# Speaker.net
KiCad netlist of a schematic drawn in EAGLE
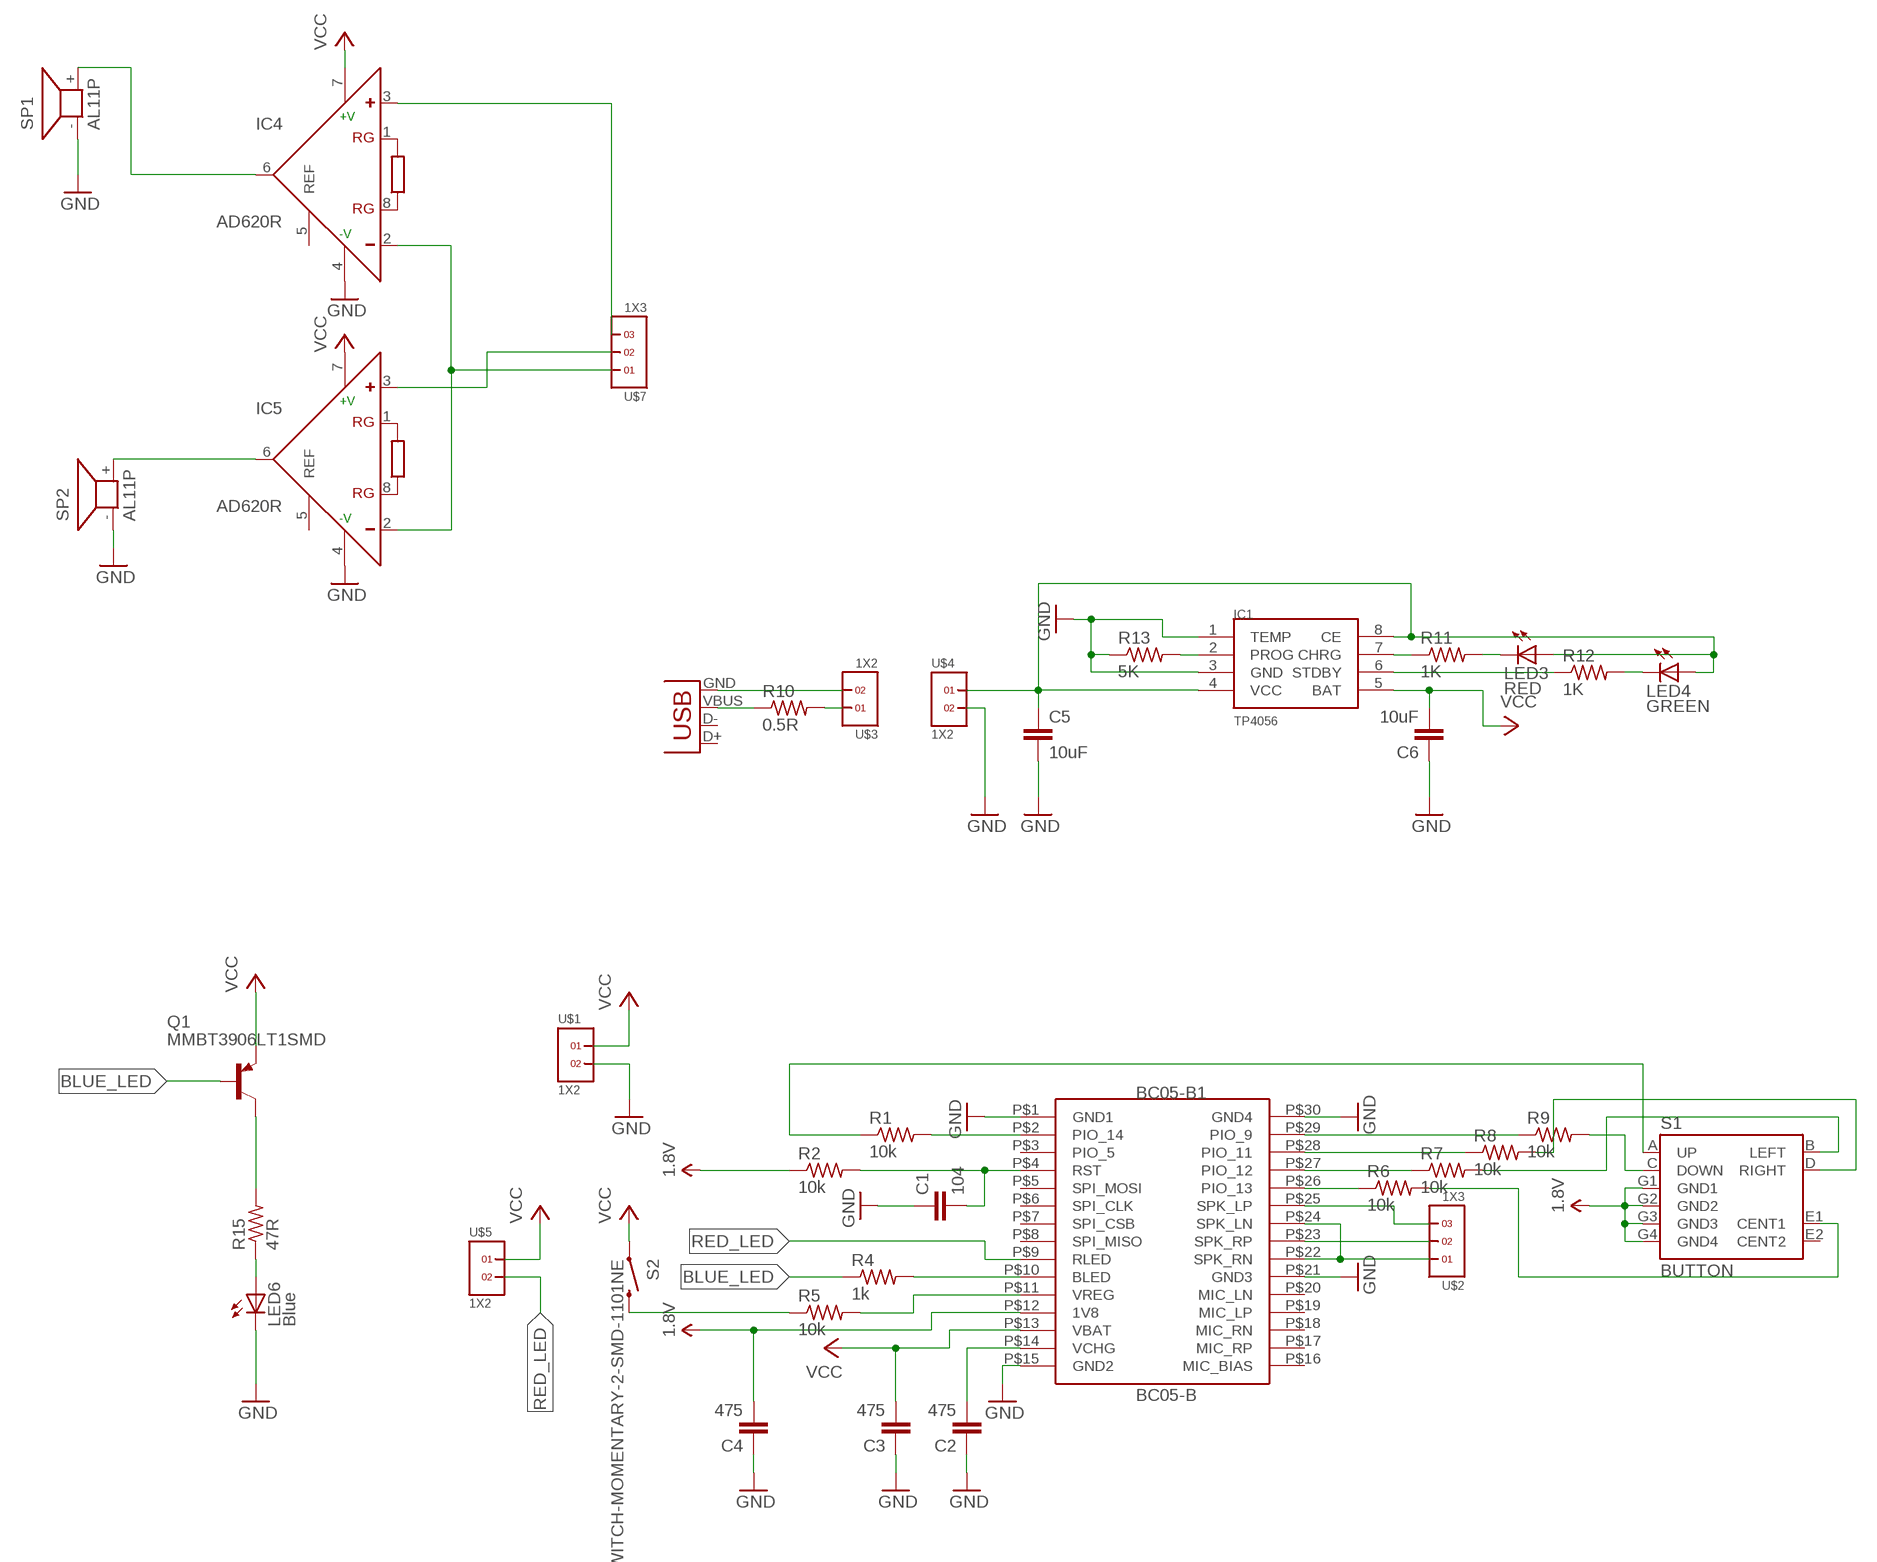
[diagram p0: schematic, sheet 1]

(export (version "E")
  (design (tool "Eeschema 10.0.6"))
  (components
    (comp (ref "BC05-B1")
      (value "BC05-B")
      (footprint "eagle-import:BC05-B")
      (libsource (lib "eagle-import") (part "BC05-B"))
    )
    (comp (ref "C1")
      (value "104")
      (footprint "eagle-import:C0603K")
      (libsource (lib "eagle-import") (part "C-EUC0603K"))
    )
    (comp (ref "C2")
      (value "475")
      (footprint "eagle-import:C0603K")
      (libsource (lib "eagle-import") (part "C-EUC0603K"))
    )
    (comp (ref "C3")
      (value "475")
      (footprint "eagle-import:C0603K")
      (libsource (lib "eagle-import") (part "C-EUC0603K"))
    )
    (comp (ref "C4")
      (value "475")
      (footprint "eagle-import:C0603K")
      (libsource (lib "eagle-import") (part "C-EUC0603K"))
    )
    (comp (ref "C5")
      (value "10uF")
      (footprint "eagle-import:C0805K")
      (libsource (lib "eagle-import") (part "C-EUC0805K"))
    )
    (comp (ref "C6")
      (value "10uF")
      (footprint "eagle-import:C0805K")
      (libsource (lib "eagle-import") (part "C-EUC0805K"))
    )
    (comp (ref "IC1")
      (value "TP4056")
      (footprint "eagle-import:SOP-8")
      (libsource (lib "eagle-import") (part "TP4056"))
    )
    (comp (ref "IC4")
      (value "AD620R")
      (footprint "eagle-import:SO8")
      (fields (field (name "MPN") "AD620AR"))
      (libsource (lib "eagle-import") (part "AD620R"))
    )
    (comp (ref "IC5")
      (value "AD620R")
      (footprint "eagle-import:SO8")
      (fields (field (name "MPN") "AD620AR"))
      (libsource (lib "eagle-import") (part "AD620R"))
    )
    (comp (ref "LED3")
      (value "RED")
      (footprint "eagle-import:CHIP-LED0805")
      (libsource (lib "eagle-import") (part "LEDCHIP-LED0805"))
    )
    (comp (ref "LED4")
      (value "GREEN")
      (footprint "eagle-import:CHIP-LED0805")
      (libsource (lib "eagle-import") (part "LEDCHIP-LED0805"))
    )
    (comp (ref "LED6")
      (value "Blue")
      (footprint "eagle-import:CHIP-LED0805")
      (libsource (lib "eagle-import") (part "LEDCHIP-LED0805"))
    )
    (comp (ref "Q1")
      (value "MMBT3906LT1SMD")
      (footprint "eagle-import:SOT23-BEC")
      (libsource (lib "eagle-import") (part "MMBT3906SMDLT1"))
    )
    (comp (ref "R1")
      (value "10k")
      (footprint "eagle-import:R0603")
      (libsource (lib "eagle-import") (part "R-US_R0603"))
    )
    (comp (ref "R2")
      (value "10k")
      (footprint "eagle-import:R0603")
      (libsource (lib "eagle-import") (part "R-US_R0603"))
    )
    (comp (ref "R4")
      (value "1k")
      (footprint "eagle-import:R0603")
      (libsource (lib "eagle-import") (part "R-US_R0603"))
    )
    (comp (ref "R5")
      (value "10k")
      (footprint "eagle-import:R0603")
      (libsource (lib "eagle-import") (part "R-US_R0603"))
    )
    (comp (ref "R6")
      (value "10k")
      (footprint "eagle-import:R0603")
      (libsource (lib "eagle-import") (part "R-US_R0603"))
    )
    (comp (ref "R7")
      (value "10k")
      (footprint "eagle-import:R0603")
      (libsource (lib "eagle-import") (part "R-US_R0603"))
    )
    (comp (ref "R8")
      (value "10k")
      (footprint "eagle-import:R0603")
      (libsource (lib "eagle-import") (part "R-US_R0603"))
    )
    (comp (ref "R9")
      (value "10k")
      (footprint "eagle-import:R0603")
      (libsource (lib "eagle-import") (part "R-US_R0603"))
    )
    (comp (ref "R10")
      (value "0.5R")
      (footprint "eagle-import:M0805")
      (libsource (lib "eagle-import") (part "R-US_M0805"))
    )
    (comp (ref "R11")
      (value "1K")
      (footprint "eagle-import:R0603")
      (libsource (lib "eagle-import") (part "R-US_R0603"))
    )
    (comp (ref "R12")
      (value "1K")
      (footprint "eagle-import:R0603")
      (libsource (lib "eagle-import") (part "R-US_R0603"))
    )
    (comp (ref "R13")
      (value "5K")
      (footprint "eagle-import:R0603")
      (libsource (lib "eagle-import") (part "R-US_R0603"))
    )
    (comp (ref "R15")
      (value "47R")
      (footprint "eagle-import:R0603")
      (libsource (lib "eagle-import") (part "R-US_R0603"))
    )
    (comp (ref "S1")
      (value "BUTTON")
      (footprint "eagle-import:BUTTON")
      (libsource (lib "eagle-import") (part "BUTTON"))
    )
    (comp (ref "S2")
      (value "SWITCH-MOMENTARY-2-SMD-1101NE")
      (footprint "eagle-import:TACTILE-SWITCH-1101NE")
      (libsource (lib "eagle-import") (part "SWITCH-MOMENTARY-2-SMD-1101NE"))
    )
    (comp (ref "SP1")
      (value "AL11P")
      (footprint "eagle-import:AL11P")
      (libsource (lib "eagle-import") (part "AL11P"))
    )
    (comp (ref "SP2")
      (value "AL11P")
      (footprint "eagle-import:AL11P")
      (libsource (lib "eagle-import") (part "AL11P"))
    )
    (comp (ref "U$1")
      (value "1X2")
      (footprint "eagle-import:1X2")
      (libsource (lib "eagle-import") (part "1X2"))
    )
    (comp (ref "U$2")
      (value "1X3")
      (footprint "eagle-import:1X3")
      (libsource (lib "eagle-import") (part "1X3"))
    )
    (comp (ref "U$3")
      (value "1X2")
      (footprint "eagle-import:1X2")
      (libsource (lib "eagle-import") (part "1X2"))
    )
    (comp (ref "U$4")
      (value "1X2")
      (footprint "eagle-import:1X2")
      (libsource (lib "eagle-import") (part "1X2"))
    )
    (comp (ref "U$5")
      (value "1X2")
      (footprint "eagle-import:1X2")
      (libsource (lib "eagle-import") (part "1X2"))
    )
    (comp (ref "U$7")
      (value "1X3")
      (footprint "eagle-import:1X3")
      (libsource (lib "eagle-import") (part "1X3"))
    )
    (comp (ref "X1")
      (value "USB-MICROB")
      (footprint "eagle-import:USB-MICROB")
      (libsource (lib "eagle-import") (part "USB-MICROB"))
    )
  )
  (nets
    (net (code "1") (name "1.8V") (class "Default")
      (node (ref "BC05-B1") (pin "P$12") (pinfunction "1V8_P$12") (pintype "bidirectional"))
      (node (ref "C4") (pin "2") (pinfunction "2_2") (pintype "passive"))
      (node (ref "R2") (pin "1") (pinfunction "1_1") (pintype "passive"))
      (node (ref "S1") (pin "G1") (pinfunction "GND1_G1") (pintype "bidirectional"))
      (node (ref "S1") (pin "G2") (pinfunction "GND2_G2") (pintype "bidirectional"))
      (node (ref "S1") (pin "G3") (pinfunction "GND3_G3") (pintype "bidirectional"))
      (node (ref "S1") (pin "G4") (pinfunction "GND4_G4") (pintype "bidirectional"))
    )
    (net (code "2") (name "BLUE_LED") (class "Default")
      (node (ref "Q1") (pin "B") (pinfunction "B_B") (pintype "passive"))
      (node (ref "R4") (pin "1") (pinfunction "1_1") (pintype "passive"))
    )
    (net (code "3") (name "GND") (class "Default")
      (node (ref "BC05-B1") (pin "P$1") (pinfunction "GND1_P$1") (pintype "bidirectional"))
      (node (ref "BC05-B1") (pin "P$15") (pinfunction "GND2_P$15") (pintype "bidirectional"))
      (node (ref "BC05-B1") (pin "P$21") (pinfunction "GND3_P$21") (pintype "bidirectional"))
      (node (ref "BC05-B1") (pin "P$30") (pinfunction "GND4_P$30") (pintype "bidirectional"))
      (node (ref "C1") (pin "1") (pinfunction "1_1") (pintype "passive"))
      (node (ref "C2") (pin "1") (pinfunction "1_1") (pintype "passive"))
      (node (ref "C3") (pin "1") (pinfunction "1_1") (pintype "passive"))
      (node (ref "C4") (pin "1") (pinfunction "1_1") (pintype "passive"))
      (node (ref "C5") (pin "2") (pinfunction "2_2") (pintype "passive"))
      (node (ref "C6") (pin "1") (pinfunction "1_1") (pintype "passive"))
      (node (ref "IC1") (pin "1") (pinfunction "TEMP_1") (pintype "bidirectional"))
      (node (ref "IC1") (pin "3") (pinfunction "GND_3") (pintype "bidirectional"))
      (node (ref "IC4") (pin "4") (pinfunction "-V_4") (pintype "power_in"))
      (node (ref "IC5") (pin "4") (pinfunction "-V_4") (pintype "power_in"))
      (node (ref "LED6") (pin "C") (pinfunction "C_C") (pintype "passive"))
      (node (ref "R13") (pin "1") (pinfunction "1_1") (pintype "passive"))
      (node (ref "SP1") (pin "-") (pinfunction "1_-") (pintype "passive"))
      (node (ref "SP2") (pin "-") (pinfunction "1_-") (pintype "passive"))
      (node (ref "U$1") (pin "2") (pinfunction "2_2") (pintype "bidirectional"))
      (node (ref "U$4") (pin "2") (pinfunction "2_2") (pintype "bidirectional"))
    )
    (net (code "4") (name "Net-(BC05-B1-BLED)") (class "Default")
      (node (ref "BC05-B1") (pin "P$10") (pinfunction "BLED_P$10") (pintype "bidirectional"))
      (node (ref "R4") (pin "2") (pinfunction "2_2") (pintype "passive"))
    )
    (net (code "5") (name "Net-(BC05-B1-PIO_9)") (class "Default")
      (node (ref "BC05-B1") (pin "P$29") (pinfunction "PIO_9_P$29") (pintype "bidirectional"))
      (node (ref "R9") (pin "1") (pinfunction "1_1") (pintype "passive"))
    )
    (net (code "6") (name "Net-(BC05-B1-PIO_11)") (class "Default")
      (node (ref "BC05-B1") (pin "P$28") (pinfunction "PIO_11_P$28") (pintype "bidirectional"))
      (node (ref "R8") (pin "1") (pinfunction "1_1") (pintype "passive"))
    )
    (net (code "7") (name "Net-(BC05-B1-PIO_12)") (class "Default")
      (node (ref "BC05-B1") (pin "P$27") (pinfunction "PIO_12_P$27") (pintype "bidirectional"))
      (node (ref "R7") (pin "1") (pinfunction "1_1") (pintype "passive"))
    )
    (net (code "8") (name "Net-(BC05-B1-PIO_13)") (class "Default")
      (node (ref "BC05-B1") (pin "P$26") (pinfunction "PIO_13_P$26") (pintype "bidirectional"))
      (node (ref "R6") (pin "1") (pinfunction "1_1") (pintype "passive"))
    )
    (net (code "9") (name "Net-(BC05-B1-PIO_14)") (class "Default")
      (node (ref "BC05-B1") (pin "P$2") (pinfunction "PIO_14_P$2") (pintype "bidirectional"))
      (node (ref "R1") (pin "2") (pinfunction "2_2") (pintype "passive"))
    )
    (net (code "10") (name "Net-(BC05-B1-RST)") (class "Default")
      (node (ref "BC05-B1") (pin "P$4") (pinfunction "RST_P$4") (pintype "bidirectional"))
      (node (ref "C1") (pin "2") (pinfunction "2_2") (pintype "passive"))
      (node (ref "R2") (pin "2") (pinfunction "2_2") (pintype "passive"))
    )
    (net (code "11") (name "Net-(BC05-B1-SPK_LN)") (class "Default")
      (node (ref "BC05-B1") (pin "P$22") (pinfunction "SPK_RN_P$22") (pintype "bidirectional"))
      (node (ref "BC05-B1") (pin "P$24") (pinfunction "SPK_LN_P$24") (pintype "bidirectional"))
      (node (ref "U$2") (pin "1") (pinfunction "1_1") (pintype "bidirectional"))
    )
    (net (code "12") (name "Net-(BC05-B1-SPK_LP)") (class "Default")
      (node (ref "BC05-B1") (pin "P$25") (pinfunction "SPK_LP_P$25") (pintype "bidirectional"))
      (node (ref "U$2") (pin "3") (pinfunction "3_3") (pintype "bidirectional"))
    )
    (net (code "13") (name "Net-(BC05-B1-SPK_RP)") (class "Default")
      (node (ref "BC05-B1") (pin "P$23") (pinfunction "SPK_RP_P$23") (pintype "bidirectional"))
      (node (ref "U$2") (pin "2") (pinfunction "2_2") (pintype "bidirectional"))
    )
    (net (code "14") (name "Net-(BC05-B1-VCHG)") (class "Default")
      (node (ref "BC05-B1") (pin "P$14") (pinfunction "VCHG_P$14") (pintype "bidirectional"))
      (node (ref "C2") (pin "2") (pinfunction "2_2") (pintype "passive"))
    )
    (net (code "15") (name "Net-(BC05-B1-VREG)") (class "Default")
      (node (ref "BC05-B1") (pin "P$11") (pinfunction "VREG_P$11") (pintype "bidirectional"))
      (node (ref "R5") (pin "2") (pinfunction "2_2") (pintype "passive"))
    )
    (net (code "16") (name "Net-(IC1-CE)") (class "Default")
      (node (ref "C5") (pin "1") (pinfunction "1_1") (pintype "passive"))
      (node (ref "IC1") (pin "4") (pinfunction "VCC_4") (pintype "bidirectional"))
      (node (ref "IC1") (pin "8") (pinfunction "CE_8") (pintype "bidirectional"))
      (node (ref "LED3") (pin "A") (pinfunction "A_A") (pintype "passive"))
      (node (ref "LED4") (pin "A") (pinfunction "A_A") (pintype "passive"))
      (node (ref "U$4") (pin "1") (pinfunction "1_1") (pintype "bidirectional"))
    )
    (net (code "17") (name "Net-(IC1-CHRG)") (class "Default")
      (node (ref "IC1") (pin "7") (pinfunction "CHRG_7") (pintype "bidirectional"))
      (node (ref "R11") (pin "1") (pinfunction "1_1") (pintype "passive"))
    )
    (net (code "18") (name "Net-(IC1-PROG)") (class "Default")
      (node (ref "IC1") (pin "2") (pinfunction "PROG_2") (pintype "bidirectional"))
      (node (ref "R13") (pin "2") (pinfunction "2_2") (pintype "passive"))
    )
    (net (code "19") (name "Net-(IC1-STDBY)") (class "Default")
      (node (ref "IC1") (pin "6") (pinfunction "STDBY_6") (pintype "bidirectional"))
      (node (ref "R12") (pin "1") (pinfunction "1_1") (pintype "passive"))
    )
    (net (code "20") (name "Net-(IC4-+)") (class "Default")
      (node (ref "IC4") (pin "3") (pinfunction "+_3") (pintype "input"))
      (node (ref "U$7") (pin "3") (pinfunction "3_3") (pintype "bidirectional"))
    )
    (net (code "21") (name "Net-(IC4--)") (class "Default")
      (node (ref "IC4") (pin "2") (pinfunction "-_2") (pintype "input"))
      (node (ref "IC5") (pin "2") (pinfunction "-_2") (pintype "input"))
      (node (ref "U$7") (pin "1") (pinfunction "1_1") (pintype "bidirectional"))
    )
    (net (code "22") (name "Net-(IC4-OUT)") (class "Default")
      (node (ref "IC4") (pin "6") (pinfunction "OUT_6") (pintype "output"))
      (node (ref "SP1") (pin "+") (pinfunction "2_+") (pintype "passive"))
    )
    (net (code "23") (name "Net-(IC5-+)") (class "Default")
      (node (ref "IC5") (pin "3") (pinfunction "+_3") (pintype "input"))
      (node (ref "U$7") (pin "2") (pinfunction "2_2") (pintype "bidirectional"))
    )
    (net (code "24") (name "Net-(IC5-OUT)") (class "Default")
      (node (ref "IC5") (pin "6") (pinfunction "OUT_6") (pintype "output"))
      (node (ref "SP2") (pin "+") (pinfunction "2_+") (pintype "passive"))
    )
    (net (code "25") (name "Net-(LED3-PadC)") (class "Default")
      (node (ref "LED3") (pin "C") (pinfunction "C_C") (pintype "passive"))
      (node (ref "R11") (pin "2") (pinfunction "2_2") (pintype "passive"))
    )
    (net (code "26") (name "Net-(LED4-PadC)") (class "Default")
      (node (ref "LED4") (pin "C") (pinfunction "C_C") (pintype "passive"))
      (node (ref "R12") (pin "2") (pinfunction "2_2") (pintype "passive"))
    )
    (net (code "27") (name "Net-(LED6-PadA)") (class "Default")
      (node (ref "LED6") (pin "A") (pinfunction "A_A") (pintype "passive"))
      (node (ref "R15") (pin "1") (pinfunction "1_1") (pintype "passive"))
    )
    (net (code "28") (name "Net-(Q1-PadC)") (class "Default")
      (node (ref "Q1") (pin "C") (pinfunction "C_C") (pintype "passive"))
      (node (ref "R15") (pin "2") (pinfunction "2_2") (pintype "passive"))
    )
    (net (code "29") (name "Net-(R10-Pad1)") (class "Default")
      (node (ref "R10") (pin "1") (pinfunction "1_1") (pintype "passive"))
      (node (ref "X1") (pin "VBUS") (pinfunction "VBUS_VBUS") (pintype "bidirectional"))
    )
    (net (code "30") (name "Net-(R10-Pad2)") (class "Default")
      (node (ref "R10") (pin "2") (pinfunction "2_2") (pintype "passive"))
      (node (ref "U$3") (pin "1") (pinfunction "1_1") (pintype "bidirectional"))
    )
    (net (code "31") (name "Net-(S1-CENT1)") (class "Default")
      (node (ref "R6") (pin "2") (pinfunction "2_2") (pintype "passive"))
      (node (ref "S1") (pin "E1") (pinfunction "CENT1_E1") (pintype "bidirectional"))
    )
    (net (code "32") (name "Net-(S1-DOWN)") (class "Default")
      (node (ref "R9") (pin "2") (pinfunction "2_2") (pintype "passive"))
      (node (ref "S1") (pin "C") (pinfunction "DOWN_C") (pintype "bidirectional"))
    )
    (net (code "33") (name "Net-(S1-LEFT)") (class "Default")
      (node (ref "R7") (pin "2") (pinfunction "2_2") (pintype "passive"))
      (node (ref "S1") (pin "B") (pinfunction "LEFT_B") (pintype "bidirectional"))
    )
    (net (code "34") (name "Net-(S1-RIGHT)") (class "Default")
      (node (ref "R8") (pin "2") (pinfunction "2_2") (pintype "passive"))
      (node (ref "S1") (pin "D") (pinfunction "RIGHT_D") (pintype "bidirectional"))
    )
    (net (code "35") (name "Net-(S1-UP)") (class "Default")
      (node (ref "R1") (pin "1") (pinfunction "1_1") (pintype "passive"))
      (node (ref "S1") (pin "A") (pinfunction "UP_A") (pintype "bidirectional"))
    )
    (net (code "36") (name "Net-(S2-2)") (class "Default")
      (node (ref "R5") (pin "1") (pinfunction "1_1") (pintype "passive"))
      (node (ref "S2") (pin "P$2") (pinfunction "2_P$2") (pintype "passive"))
    )
    (net (code "37") (name "Net-(U$3-Pad2)") (class "Default")
      (node (ref "U$3") (pin "2") (pinfunction "2_2") (pintype "bidirectional"))
      (node (ref "X1") (pin "GND") (pinfunction "GND_GND") (pintype "bidirectional"))
    )
    (net (code "38") (name "RED_LED") (class "Default")
      (node (ref "BC05-B1") (pin "P$9") (pinfunction "RLED_P$9") (pintype "bidirectional"))
      (node (ref "U$5") (pin "2") (pinfunction "2_2") (pintype "bidirectional"))
    )
    (net (code "39") (name "VCC") (class "Default")
      (node (ref "BC05-B1") (pin "P$13") (pinfunction "VBAT_P$13") (pintype "bidirectional"))
      (node (ref "C3") (pin "2") (pinfunction "2_2") (pintype "passive"))
      (node (ref "C6") (pin "2") (pinfunction "2_2") (pintype "passive"))
      (node (ref "IC1") (pin "5") (pinfunction "BAT_5") (pintype "bidirectional"))
      (node (ref "IC4") (pin "7") (pinfunction "+V_7") (pintype "power_in"))
      (node (ref "IC5") (pin "7") (pinfunction "+V_7") (pintype "power_in"))
      (node (ref "Q1") (pin "E") (pinfunction "E_E") (pintype "passive"))
      (node (ref "S2") (pin "P$1") (pinfunction "1_P$1") (pintype "passive"))
      (node (ref "U$1") (pin "1") (pinfunction "1_1") (pintype "bidirectional"))
      (node (ref "U$5") (pin "1") (pinfunction "1_1") (pintype "bidirectional"))
    )
    (net (code "40") (name "unconnected-(BC05-B1-MIC_BIAS-PadP$16)") (class "Default")
      (node (ref "BC05-B1") (pin "P$16") (pinfunction "MIC_BIAS_P$16") (pintype "bidirectional"))
    )
    (net (code "41") (name "unconnected-(BC05-B1-MIC_LN-PadP$20)") (class "Default")
      (node (ref "BC05-B1") (pin "P$20") (pinfunction "MIC_LN_P$20") (pintype "bidirectional"))
    )
    (net (code "42") (name "unconnected-(BC05-B1-MIC_LP-PadP$19)") (class "Default")
      (node (ref "BC05-B1") (pin "P$19") (pinfunction "MIC_LP_P$19") (pintype "bidirectional"))
    )
    (net (code "43") (name "unconnected-(BC05-B1-MIC_RN-PadP$18)") (class "Default")
      (node (ref "BC05-B1") (pin "P$18") (pinfunction "MIC_RN_P$18") (pintype "bidirectional"))
    )
    (net (code "44") (name "unconnected-(BC05-B1-MIC_RP-PadP$17)") (class "Default")
      (node (ref "BC05-B1") (pin "P$17") (pinfunction "MIC_RP_P$17") (pintype "bidirectional"))
    )
    (net (code "45") (name "unconnected-(BC05-B1-PIO_5-PadP$3)") (class "Default")
      (node (ref "BC05-B1") (pin "P$3") (pinfunction "PIO_5_P$3") (pintype "bidirectional"))
    )
    (net (code "46") (name "unconnected-(BC05-B1-SPI_CLK-PadP$6)") (class "Default")
      (node (ref "BC05-B1") (pin "P$6") (pinfunction "SPI_CLK_P$6") (pintype "bidirectional"))
    )
    (net (code "47") (name "unconnected-(BC05-B1-SPI_CSB-PadP$7)") (class "Default")
      (node (ref "BC05-B1") (pin "P$7") (pinfunction "SPI_CSB_P$7") (pintype "bidirectional"))
    )
    (net (code "48") (name "unconnected-(BC05-B1-SPI_MISO-PadP$8)") (class "Default")
      (node (ref "BC05-B1") (pin "P$8") (pinfunction "SPI_MISO_P$8") (pintype "bidirectional"))
    )
    (net (code "49") (name "unconnected-(BC05-B1-SPI_MOSI-PadP$5)") (class "Default")
      (node (ref "BC05-B1") (pin "P$5") (pinfunction "SPI_MOSI_P$5") (pintype "bidirectional"))
    )
    (net (code "50") (name "unconnected-(IC4-REF-Pad5)") (class "Default")
      (node (ref "IC4") (pin "5") (pinfunction "REF_5") (pintype "passive"))
    )
    (net (code "51") (name "unconnected-(IC4-RG-Pad1)") (class "Default")
      (node (ref "IC4") (pin "1") (pinfunction "RG_1") (pintype "passive"))
    )
    (net (code "52") (name "unconnected-(IC4-RG-Pad8)") (class "Default")
      (node (ref "IC4") (pin "8") (pinfunction "RG_8") (pintype "passive"))
    )
    (net (code "53") (name "unconnected-(IC5-REF-Pad5)") (class "Default")
      (node (ref "IC5") (pin "5") (pinfunction "REF_5") (pintype "passive"))
    )
    (net (code "54") (name "unconnected-(IC5-RG-Pad1)") (class "Default")
      (node (ref "IC5") (pin "1") (pinfunction "RG_1") (pintype "passive"))
    )
    (net (code "55") (name "unconnected-(IC5-RG-Pad8)") (class "Default")
      (node (ref "IC5") (pin "8") (pinfunction "RG_8") (pintype "passive"))
    )
    (net (code "56") (name "unconnected-(S1-CENT2-PadE2)") (class "Default")
      (node (ref "S1") (pin "E2") (pinfunction "CENT2_E2") (pintype "bidirectional"))
    )
    (net (code "57") (name "unconnected-(X1-PadD+)") (class "Default")
      (node (ref "X1") (pin "D+") (pinfunction "D+_D+") (pintype "bidirectional"))
    )
    (net (code "58") (name "unconnected-(X1-PadD-)") (class "Default")
      (node (ref "X1") (pin "D-") (pinfunction "D-_D-") (pintype "bidirectional"))
    )
  )
)
